# Communication_Main.net
KiCad netlist of a schematic drawn in Altium Designer
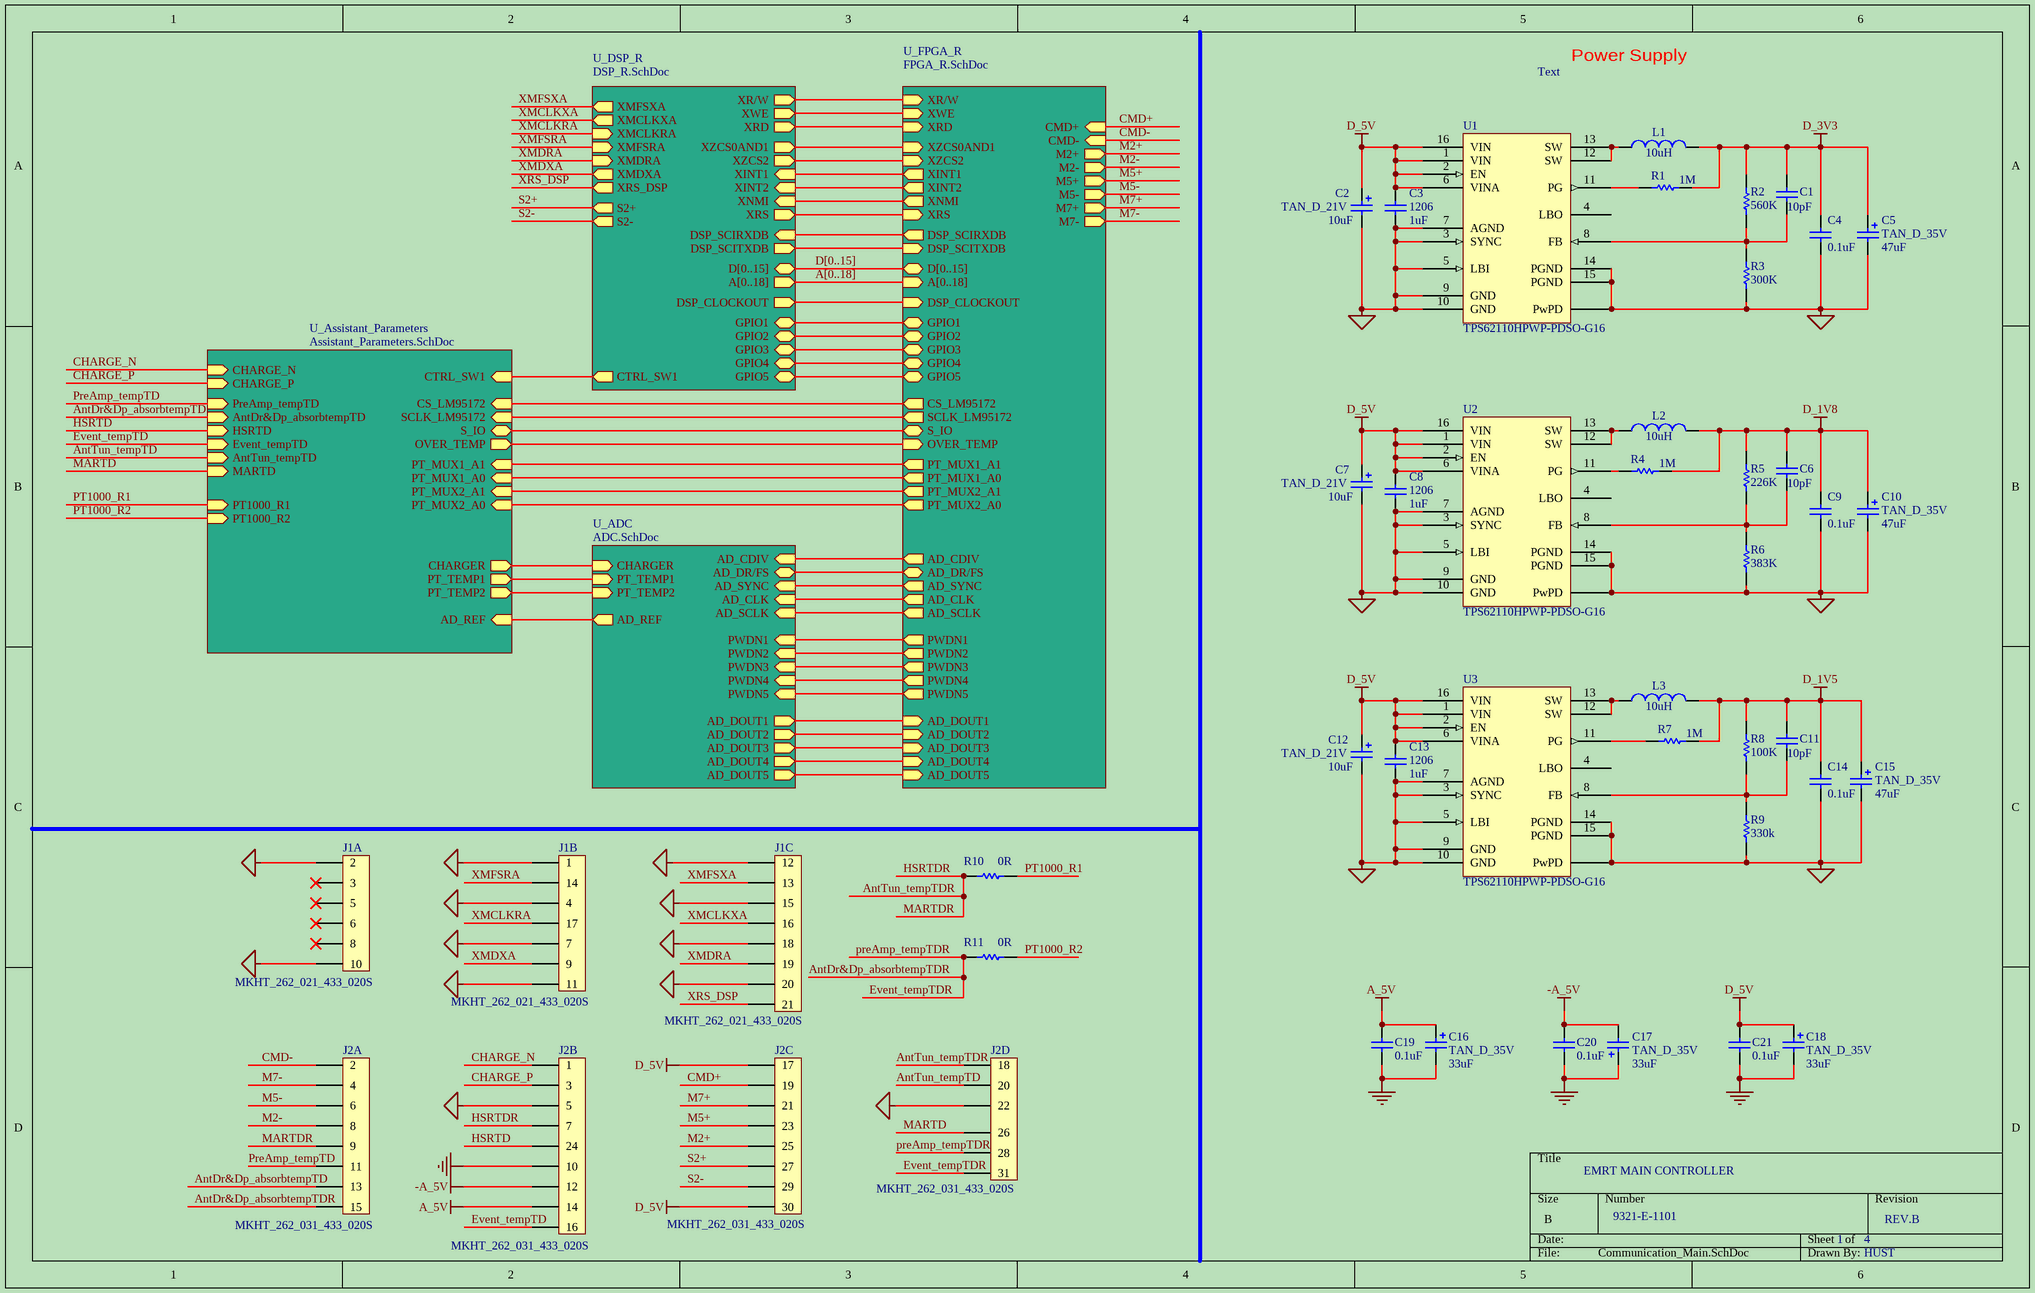
[diagram p0: Communication_Main.SchDoc]

(export (version "E")
  (design (tool "Eeschema 10.0.6"))
  (components
    (comp (ref "C1")
      (value "10pF")
      (footprint "CAPS0805_57")
      (description "Capacitor")
      (fields (field (name "PART NUMBER") "Y20025162") (field (name "Comment") "Cap"))
      (libsource (lib "Cap") (part "Cap"))
    )
    (comp (ref "C2")
      (value "TAN_D_21V")
      (footprint "EMRT MAIN CONTROLLER:CAPSP_2q2917")
      (description "Polarized Capacitor")
      (fields (field (name "ALTIUM_VALUE") "10uF") (field (name "PART NUMBER") "Y20024818"))
      (libsource (lib "电容") (part "Y20024818"))
    )
    (comp (ref "C3")
      (value "1206")
      (footprint "CAPS1206_43")
      (description "Capacitor")
      (fields (field (name "ALTIUM_VALUE") "1uF") (field (name "PART NUMBER") "Y20024113"))
      (libsource (lib "Cap") (part "Cap"))
    )
    (comp (ref "C4")
      (value "0.1uF")
      (footprint "CAPS0805_57")
      (description "Capacitor")
      (fields (field (name "PART NUMBER") "Y20025084") (field (name "Comment") "Cap"))
      (libsource (lib "Cap") (part "Cap"))
    )
    (comp (ref "C5")
      (value "TAN_D_35V")
      (footprint "CAPSP_2q2917")
      (description "Polarized Capacitor")
      (fields (field (name "ALTIUM_VALUE") "47uF") (field (name "PART NUMBER") "Y20024816"))
      (libsource (lib "Cap Pol") (part "Cap Pol"))
    )
    (comp (ref "C6")
      (value "10pF")
      (footprint "CAPS0805_57")
      (description "Capacitor")
      (fields (field (name "PART NUMBER") "Y20025162") (field (name "Comment") "Cap"))
      (libsource (lib "Cap") (part "Cap"))
    )
    (comp (ref "C7")
      (value "TAN_D_21V")
      (footprint "EMRT MAIN CONTROLLER:CAPSP_2q2917")
      (description "Polarized Capacitor")
      (fields (field (name "ALTIUM_VALUE") "10uF") (field (name "PART NUMBER") "Y20024818"))
      (libsource (lib "电容") (part "Y20024818"))
    )
    (comp (ref "C8")
      (value "1206")
      (footprint "CAPS1206_43")
      (description "Capacitor")
      (fields (field (name "ALTIUM_VALUE") "1uF") (field (name "PART NUMBER") "Y20024113"))
      (libsource (lib "Cap") (part "Cap"))
    )
    (comp (ref "C9")
      (value "0.1uF")
      (footprint "CAPS0805_57")
      (description "Capacitor")
      (fields (field (name "PART NUMBER") "Y20025084") (field (name "Comment") "Cap"))
      (libsource (lib "Cap") (part "Cap"))
    )
    (comp (ref "C10")
      (value "TAN_D_35V")
      (footprint "CAPSP_2q2917")
      (description "Polarized Capacitor")
      (fields (field (name "ALTIUM_VALUE") "47uF") (field (name "PART NUMBER") "Y20024816"))
      (libsource (lib "Cap Pol") (part "Cap Pol"))
    )
    (comp (ref "C11")
      (value "10pF")
      (footprint "CAPS0805_57")
      (description "Capacitor")
      (fields (field (name "PART NUMBER") "Y20025162") (field (name "Comment") "Cap"))
      (libsource (lib "Cap") (part "Cap"))
    )
    (comp (ref "C12")
      (value "TAN_D_21V")
      (footprint "EMRT MAIN CONTROLLER:CAPSP_2q2917")
      (description "Polarized Capacitor")
      (fields (field (name "ALTIUM_VALUE") "10uF") (field (name "PART NUMBER") "Y20024818"))
      (libsource (lib "电容") (part "Y20024818"))
    )
    (comp (ref "C13")
      (value "1206")
      (footprint "CAPS1206_43")
      (description "Capacitor")
      (fields (field (name "ALTIUM_VALUE") "1uF") (field (name "PART NUMBER") "Y20024113"))
      (libsource (lib "Cap") (part "Cap"))
    )
    (comp (ref "C14")
      (value "0.1uF")
      (footprint "CAPS0805_57")
      (description "Capacitor")
      (fields (field (name "PART NUMBER") "Y20025084") (field (name "Comment") "Cap"))
      (libsource (lib "Cap") (part "Cap"))
    )
    (comp (ref "C15")
      (value "TAN_D_35V")
      (footprint "CAPSP_2q2917")
      (description "Polarized Capacitor")
      (fields (field (name "ALTIUM_VALUE") "47uF") (field (name "PART NUMBER") "Y20024816"))
      (libsource (lib "Cap Pol") (part "Cap Pol"))
    )
    (comp (ref "C16")
      (value "TAN_D_35V")
      (footprint "CAPSP_2q2917")
      (description "Polarized Capacitor")
      (fields (field (name "ALTIUM_VALUE") "33uF") (field (name "PART NUMBER") "Y20024816"))
      (libsource (lib "Cap Pol") (part "Cap Pol"))
    )
    (comp (ref "C17")
      (value "TAN_D_35V")
      (footprint "CAPSP_2q2917")
      (description "Polarized Capacitor")
      (fields (field (name "ALTIUM_VALUE") "33uF") (field (name "PART NUMBER") "Y20024816"))
      (libsource (lib "Cap Pol") (part "Cap Pol"))
    )
    (comp (ref "C18")
      (value "TAN_D_35V")
      (footprint "CAPSP_2q2917")
      (description "Polarized Capacitor")
      (fields (field (name "ALTIUM_VALUE") "33uF") (field (name "PART NUMBER") "Y20024816"))
      (libsource (lib "Cap Pol") (part "Cap Pol"))
    )
    (comp (ref "C19")
      (value "0.1uF")
      (footprint "CAPS0805_57")
      (description "Capacitor")
      (fields (field (name "PART NUMBER") "Y20025084") (field (name "Comment") "Cap"))
      (libsource (lib "Cap") (part "Cap"))
    )
    (comp (ref "C20")
      (value "0.1uF")
      (footprint "CAPS0805_57")
      (description "Capacitor")
      (fields (field (name "PART NUMBER") "Y20025084") (field (name "Comment") "Cap"))
      (libsource (lib "Cap") (part "Cap"))
    )
    (comp (ref "C21")
      (value "0.1uF")
      (footprint "CAPS0805_57")
      (description "Capacitor")
      (fields (field (name "PART NUMBER") "Y20025084") (field (name "Comment") "Cap"))
      (libsource (lib "Cap") (part "Cap"))
    )
    (comp (ref "J1")
      (value "MKHT_262_021_433_020S")
      (footprint "MKHT_262_021_433_020S")
      (libsource (lib "srj") (part "MKHT_262_021_433_020S"))
    )
    (comp (ref "J2")
      (value "MKHT_262_031_433_020S")
      (footprint "MKHT_262_031_433_020S")
      (libsource (lib "srj") (part "MKHT_262_031_433_020S"))
    )
    (comp (ref "L1")
      (value "10uH")
      (footprint "Inductor_HT")
      (description "Inductor-1")
      (fields (field (name "PART NUMBER") "Y20028214") (field (name "Comment") "Inductor"))
      (libsource (lib "B82422H1103K000") (part "B82422H1103K000"))
    )
    (comp (ref "L2")
      (value "10uH")
      (footprint "Inductor_HT")
      (description "Inductor-1")
      (fields (field (name "PART NUMBER") "Y20028214") (field (name "Comment") "Inductor"))
      (libsource (lib "B82422H1103K000") (part "B82422H1103K000"))
    )
    (comp (ref "L3")
      (value "10uH")
      (footprint "Inductor_HT")
      (description "Inductor-1")
      (fields (field (name "PART NUMBER") "Y20028214") (field (name "Comment") "Inductor"))
      (libsource (lib "B82422H1103K000") (part "B82422H1103K000"))
    )
    (comp (ref "R1")
      (value "1M")
      (footprint "RESS0805")
      (description "Semiconductor Resistor")
      (fields
        (field (name "MANUFACTURER") "Generic Components")
        (field (name "Comment") "Res")
        (field (name "PUBLISHER") "Altium Hobart Technology Centre")
      )
      (libsource (lib "EMRT MAIN CONTROLLER") (part "Res"))
    )
    (comp (ref "R2")
      (value "560K")
      (footprint "RESS0805")
      (description "Semiconductor Resistor")
      (fields
        (field (name "MANUFACTURER") "Generic Components")
        (field (name "Comment") "Res")
        (field (name "PUBLISHER") "Altium Hobart Technology Centre")
      )
      (libsource (lib "EMRT MAIN CONTROLLER") (part "Res"))
    )
    (comp (ref "R3")
      (value "300K")
      (footprint "RESS0805")
      (description "Semiconductor Resistor")
      (fields
        (field (name "MANUFACTURER") "Generic Components")
        (field (name "Comment") "Res")
        (field (name "PUBLISHER") "Altium Hobart Technology Centre")
      )
      (libsource (lib "EMRT MAIN CONTROLLER") (part "Res"))
    )
    (comp (ref "R4")
      (value "1M")
      (footprint "RESS0805")
      (description "Semiconductor Resistor")
      (fields
        (field (name "MANUFACTURER") "Generic Components")
        (field (name "Comment") "Res")
        (field (name "PUBLISHER") "Altium Hobart Technology Centre")
      )
      (libsource (lib "EMRT MAIN CONTROLLER") (part "Res"))
    )
    (comp (ref "R5")
      (value "226K")
      (footprint "RESS0805")
      (description "Semiconductor Resistor")
      (fields
        (field (name "MANUFACTURER") "Generic Components")
        (field (name "Comment") "Res")
        (field (name "PUBLISHER") "Altium Hobart Technology Centre")
      )
      (libsource (lib "EMRT MAIN CONTROLLER") (part "Res"))
    )
    (comp (ref "R6")
      (value "383K")
      (footprint "RESS0805")
      (description "Semiconductor Resistor")
      (fields
        (field (name "MANUFACTURER") "Generic Components")
        (field (name "Comment") "Res")
        (field (name "PUBLISHER") "Altium Hobart Technology Centre")
      )
      (libsource (lib "EMRT MAIN CONTROLLER") (part "Res"))
    )
    (comp (ref "R7")
      (value "1M")
      (footprint "RESS0805")
      (description "Semiconductor Resistor")
      (fields
        (field (name "MANUFACTURER") "Generic Components")
        (field (name "Comment") "Res")
        (field (name "PUBLISHER") "Altium Hobart Technology Centre")
      )
      (libsource (lib "EMRT MAIN CONTROLLER") (part "Res"))
    )
    (comp (ref "R8")
      (value "100K")
      (footprint "RESS0805")
      (description "Semiconductor Resistor")
      (fields
        (field (name "MANUFACTURER") "Generic Components")
        (field (name "Comment") "Res")
        (field (name "PUBLISHER") "Altium Hobart Technology Centre")
      )
      (libsource (lib "EMRT MAIN CONTROLLER") (part "Res"))
    )
    (comp (ref "R9")
      (value "330k")
      (footprint "RESS0805")
      (description "Semiconductor Resistor")
      (fields
        (field (name "MANUFACTURER") "Generic Components")
        (field (name "Comment") "Res")
        (field (name "PUBLISHER") "Altium Hobart Technology Centre")
      )
      (libsource (lib "EMRT MAIN CONTROLLER") (part "Res"))
    )
    (comp (ref "R10")
      (value "0R")
      (footprint "RESS0805")
      (description "Semiconductor Resistor")
      (fields
        (field (name "MANUFACTURER") "Generic Components")
        (field (name "Comment") "Res")
        (field (name "PUBLISHER") "Altium Hobart Technology Centre")
      )
      (libsource (lib "EMRT MAIN CONTROLLER") (part "Res"))
    )
    (comp (ref "R11")
      (value "0R")
      (footprint "RESS0805")
      (description "Semiconductor Resistor")
      (fields
        (field (name "MANUFACTURER") "Generic Components")
        (field (name "Comment") "Res")
        (field (name "PUBLISHER") "Altium Hobart Technology Centre")
      )
      (libsource (lib "EMRT MAIN CONTROLLER") (part "Res"))
    )
    (comp (ref "U1")
      (value "TPS62110HPWP-PDSO-G16")
      (footprint "EMRT MAIN CONTROLLER:PWP16")
      (fields (field (name "PART NUMBER") "Y20033002"))
      (libsource (lib "TPS62110-HT") (part "TPS62110-HPWP"))
    )
    (comp (ref "U2")
      (value "TPS62110HPWP-PDSO-G16")
      (footprint "EMRT MAIN CONTROLLER:PWP16")
      (fields (field (name "PART NUMBER") "Y20033002"))
      (libsource (lib "TPS62110-HT") (part "TPS62110-HPWP"))
    )
    (comp (ref "U3")
      (value "TPS62110HPWP-PDSO-G16")
      (footprint "EMRT MAIN CONTROLLER:PWP16")
      (fields (field (name "PART NUMBER") "Y20033002"))
      (libsource (lib "TPS62110-HT") (part "TPS62110-HPWP"))
    )
  )
  (nets
    (net (code "36") (name "-A_5V") (class "Default")
      (node (ref "C17") (pin "2") (pinfunction "2_2") (pintype "passive"))
      (node (ref "C20") (pin "1") (pinfunction "1_1") (pintype "passive"))
      (node (ref "J2") (pin "12") (pinfunction "12_12") (pintype "passive"))
    )
    (net (code "49") (name "/AntDr&Dp_absorbtempTD") (class "Default")
      (node (ref "J2") (pin "13") (pinfunction "13_13") (pintype "passive"))
    )
    (net (code "50") (name "/AntDr&Dp_absorbtempTDR") (class "Default")
      (node (ref "J2") (pin "15") (pinfunction "15_15") (pintype "passive"))
      (node (ref "J2") (pin "28") (pinfunction "28_28") (pintype "passive"))
      (node (ref "J2") (pin "31") (pinfunction "31_31") (pintype "passive"))
      (node (ref "R11") (pin "2") (pinfunction "2_2") (pintype "passive"))
    )
    (net (code "51") (name "/AntTun_tempTD") (class "Default")
      (node (ref "J2") (pin "20") (pinfunction "20_20") (pintype "passive"))
    )
    (net (code "52") (name "/AntTun_tempTDR") (class "Default")
      (node (ref "J2") (pin "18") (pinfunction "18_18") (pintype "passive"))
      (node (ref "J2") (pin "7") (pinfunction "7_7") (pintype "passive"))
      (node (ref "J2") (pin "9") (pinfunction "9_9") (pintype "passive"))
      (node (ref "R10") (pin "2") (pinfunction "2_2") (pintype "passive"))
    )
    (net (code "54") (name "/CHARGE_N") (class "Default")
      (node (ref "J2") (pin "1") (pinfunction "1_1") (pintype "passive"))
    )
    (net (code "55") (name "/CHARGE_P") (class "Default")
      (node (ref "J2") (pin "3") (pinfunction "3_3") (pintype "passive"))
    )
    (net (code "56") (name "/CMD+") (class "Default")
      (node (ref "J2") (pin "19") (pinfunction "19_19") (pintype "passive"))
    )
    (net (code "57") (name "/CMD-") (class "Default")
      (node (ref "J2") (pin "2") (pinfunction "2_2") (pintype "passive"))
    )
    (net (code "64") (name "/Event_tempTD") (class "Default")
      (node (ref "J2") (pin "16") (pinfunction "16_16") (pintype "passive"))
    )
    (net (code "70") (name "/HSRTD") (class "Default")
      (node (ref "J2") (pin "24") (pinfunction "24_24") (pintype "passive"))
    )
    (net (code "71") (name "/M2+") (class "Default")
      (node (ref "J2") (pin "25") (pinfunction "25_25") (pintype "passive"))
    )
    (net (code "72") (name "/M2-") (class "Default")
      (node (ref "J2") (pin "8") (pinfunction "8_8") (pintype "passive"))
    )
    (net (code "73") (name "/M5+") (class "Default")
      (node (ref "J2") (pin "23") (pinfunction "23_23") (pintype "passive"))
    )
    (net (code "74") (name "/M5-") (class "Default")
      (node (ref "J2") (pin "6") (pinfunction "6_6") (pintype "passive"))
    )
    (net (code "75") (name "/M7+") (class "Default")
      (node (ref "J2") (pin "21") (pinfunction "21_21") (pintype "passive"))
    )
    (net (code "76") (name "/M7-") (class "Default")
      (node (ref "J2") (pin "4") (pinfunction "4_4") (pintype "passive"))
    )
    (net (code "77") (name "/MARTD") (class "Default")
      (node (ref "J2") (pin "26") (pinfunction "26_26") (pintype "passive"))
    )
    (net (code "79") (name "/PT1000_R1") (class "Default")
      (node (ref "R10") (pin "1") (pinfunction "1_1") (pintype "passive"))
    )
    (net (code "80") (name "/PT1000_R2") (class "Default")
      (node (ref "R11") (pin "1") (pinfunction "1_1") (pintype "passive"))
    )
    (net (code "92") (name "/PreAmp_tempTD") (class "Default")
      (node (ref "J2") (pin "11") (pinfunction "11_11") (pintype "passive"))
    )
    (net (code "93") (name "/S2+") (class "Default")
      (node (ref "J2") (pin "27") (pinfunction "27_27") (pintype "passive"))
    )
    (net (code "94") (name "/S2-") (class "Default")
      (node (ref "J2") (pin "29") (pinfunction "29_29") (pintype "passive"))
    )
    (net (code "99") (name "/XMCLKRA") (class "Default")
      (node (ref "J1") (pin "17") (pinfunction "17_17") (pintype "passive"))
    )
    (net (code "100") (name "/XMCLKXA") (class "Default")
      (node (ref "J1") (pin "16") (pinfunction "16_16") (pintype "passive"))
    )
    (net (code "101") (name "/XMDRA") (class "Default")
      (node (ref "J1") (pin "19") (pinfunction "19_19") (pintype "passive"))
    )
    (net (code "102") (name "/XMDXA") (class "Default")
      (node (ref "J1") (pin "9") (pinfunction "9_9") (pintype "passive"))
    )
    (net (code "103") (name "/XMFSRA") (class "Default")
      (node (ref "J1") (pin "14") (pinfunction "14_14") (pintype "passive"))
    )
    (net (code "104") (name "/XMFSXA") (class "Default")
      (node (ref "J1") (pin "13") (pinfunction "13_13") (pintype "passive"))
    )
    (net (code "108") (name "/XRS_DSP") (class "Default")
      (node (ref "J1") (pin "21") (pinfunction "21_21") (pintype "passive"))
    )
    (net (code "113") (name "A_5V") (class "Default")
      (node (ref "C16") (pin "1") (pinfunction "1_1") (pintype "passive"))
      (node (ref "C19") (pin "2") (pinfunction "2_2") (pintype "passive"))
      (node (ref "J2") (pin "14") (pinfunction "14_14") (pintype "passive"))
    )
    (net (code "114") (name "DGND") (class "Default")
      (node (ref "C10") (pin "2") (pinfunction "2_2") (pintype "passive"))
      (node (ref "C12") (pin "2") (pinfunction "2_2") (pintype "passive"))
      (node (ref "C13") (pin "1") (pinfunction "1_1") (pintype "passive"))
      (node (ref "C14") (pin "1") (pinfunction "1_1") (pintype "passive"))
      (node (ref "C15") (pin "2") (pinfunction "2_2") (pintype "passive"))
      (node (ref "C2") (pin "2") (pinfunction "2_2") (pintype "passive"))
      (node (ref "C3") (pin "1") (pinfunction "1_1") (pintype "passive"))
      (node (ref "C4") (pin "1") (pinfunction "1_1") (pintype "passive"))
      (node (ref "C5") (pin "2") (pinfunction "2_2") (pintype "passive"))
      (node (ref "C7") (pin "2") (pinfunction "2_2") (pintype "passive"))
      (node (ref "C8") (pin "1") (pinfunction "1_1") (pintype "passive"))
      (node (ref "C9") (pin "1") (pinfunction "1_1") (pintype "passive"))
      (node (ref "J1") (pin "1") (pinfunction "1_1") (pintype "passive"))
      (node (ref "J1") (pin "10") (pinfunction "10_10") (pintype "passive"))
      (node (ref "J1") (pin "11") (pinfunction "11_11") (pintype "passive"))
      (node (ref "J1") (pin "12") (pinfunction "12_12") (pintype "passive"))
      (node (ref "J1") (pin "15") (pinfunction "15_15") (pintype "passive"))
      (node (ref "J1") (pin "18") (pinfunction "18_18") (pintype "passive"))
      (node (ref "J1") (pin "2") (pinfunction "2_2") (pintype "passive"))
      (node (ref "J1") (pin "20") (pinfunction "20_20") (pintype "passive"))
      (node (ref "J1") (pin "4") (pinfunction "4_4") (pintype "passive"))
      (node (ref "J1") (pin "7") (pinfunction "7_7") (pintype "passive"))
      (node (ref "J2") (pin "22") (pinfunction "22_22") (pintype "passive"))
      (node (ref "J2") (pin "5") (pinfunction "5_5") (pintype "passive"))
      (node (ref "R3") (pin "1") (pinfunction "1_1") (pintype "passive"))
      (node (ref "R6") (pin "1") (pinfunction "1_1") (pintype "passive"))
      (node (ref "R9") (pin "1") (pinfunction "1_1") (pintype "passive"))
      (node (ref "U1") (pin "10") (pinfunction "GND_10") (pintype "passive"))
      (node (ref "U1") (pin "14") (pinfunction "PGND_14") (pintype "passive"))
      (node (ref "U1") (pin "15") (pinfunction "PGND_15") (pintype "passive"))
      (node (ref "U1") (pin "3") (pinfunction "SYNC_3") (pintype "input"))
      (node (ref "U1") (pin "5") (pinfunction "LBI_5") (pintype "input"))
      (node (ref "U1") (pin "7") (pinfunction "AGND_7") (pintype "power_in"))
      (node (ref "U1") (pin "9") (pinfunction "GND_9") (pintype "passive"))
      (node (ref "U1") (pin "PwPD") (pinfunction "PwPD_PwPD") (pintype "passive"))
      (node (ref "U2") (pin "10") (pinfunction "GND_10") (pintype "passive"))
      (node (ref "U2") (pin "14") (pinfunction "PGND_14") (pintype "passive"))
      (node (ref "U2") (pin "15") (pinfunction "PGND_15") (pintype "passive"))
      (node (ref "U2") (pin "3") (pinfunction "SYNC_3") (pintype "input"))
      (node (ref "U2") (pin "5") (pinfunction "LBI_5") (pintype "input"))
      (node (ref "U2") (pin "7") (pinfunction "AGND_7") (pintype "power_in"))
      (node (ref "U2") (pin "9") (pinfunction "GND_9") (pintype "passive"))
      (node (ref "U2") (pin "PwPD") (pinfunction "PwPD_PwPD") (pintype "passive"))
      (node (ref "U3") (pin "10") (pinfunction "GND_10") (pintype "passive"))
      (node (ref "U3") (pin "14") (pinfunction "PGND_14") (pintype "passive"))
      (node (ref "U3") (pin "15") (pinfunction "PGND_15") (pintype "passive"))
      (node (ref "U3") (pin "3") (pinfunction "SYNC_3") (pintype "input"))
      (node (ref "U3") (pin "5") (pinfunction "LBI_5") (pintype "input"))
      (node (ref "U3") (pin "7") (pinfunction "AGND_7") (pintype "power_in"))
      (node (ref "U3") (pin "9") (pinfunction "GND_9") (pintype "passive"))
      (node (ref "U3") (pin "PwPD") (pinfunction "PwPD_PwPD") (pintype "passive"))
    )
    (net (code "115") (name "D_1V5") (class "Default")
      (node (ref "C11") (pin "2") (pinfunction "2_2") (pintype "passive"))
      (node (ref "C14") (pin "2") (pinfunction "2_2") (pintype "passive"))
      (node (ref "C15") (pin "1") (pinfunction "1_1") (pintype "passive"))
      (node (ref "L3") (pin "2") (pinfunction "2_2") (pintype "passive"))
      (node (ref "R7") (pin "2") (pinfunction "2_2") (pintype "passive"))
      (node (ref "R8") (pin "2") (pinfunction "2_2") (pintype "passive"))
    )
    (net (code "116") (name "D_1V8") (class "Default")
      (node (ref "C10") (pin "1") (pinfunction "1_1") (pintype "passive"))
      (node (ref "C6") (pin "2") (pinfunction "2_2") (pintype "passive"))
      (node (ref "C9") (pin "2") (pinfunction "2_2") (pintype "passive"))
      (node (ref "L2") (pin "2") (pinfunction "2_2") (pintype "passive"))
      (node (ref "R4") (pin "2") (pinfunction "2_2") (pintype "passive"))
      (node (ref "R5") (pin "2") (pinfunction "2_2") (pintype "passive"))
    )
    (net (code "117") (name "D_3V3") (class "Default")
      (node (ref "C1") (pin "2") (pinfunction "2_2") (pintype "passive"))
      (node (ref "C4") (pin "2") (pinfunction "2_2") (pintype "passive"))
      (node (ref "C5") (pin "1") (pinfunction "1_1") (pintype "passive"))
      (node (ref "L1") (pin "2") (pinfunction "2_2") (pintype "passive"))
      (node (ref "R1") (pin "2") (pinfunction "2_2") (pintype "passive"))
      (node (ref "R2") (pin "2") (pinfunction "2_2") (pintype "passive"))
    )
    (net (code "118") (name "D_5V") (class "Default")
      (node (ref "C12") (pin "1") (pinfunction "1_1") (pintype "passive"))
      (node (ref "C13") (pin "2") (pinfunction "2_2") (pintype "passive"))
      (node (ref "C18") (pin "1") (pinfunction "1_1") (pintype "passive"))
      (node (ref "C2") (pin "1") (pinfunction "1_1") (pintype "passive"))
      (node (ref "C21") (pin "1") (pinfunction "1_1") (pintype "passive"))
      (node (ref "C3") (pin "2") (pinfunction "2_2") (pintype "passive"))
      (node (ref "C7") (pin "1") (pinfunction "1_1") (pintype "passive"))
      (node (ref "C8") (pin "2") (pinfunction "2_2") (pintype "passive"))
      (node (ref "J2") (pin "17") (pinfunction "17_17") (pintype "passive"))
      (node (ref "J2") (pin "30") (pinfunction "30_30") (pintype "passive"))
      (node (ref "U1") (pin "1") (pinfunction "VIN_1") (pintype "power_in"))
      (node (ref "U1") (pin "16") (pinfunction "VIN_16") (pintype "power_in"))
      (node (ref "U1") (pin "2") (pinfunction "EN_2") (pintype "input"))
      (node (ref "U1") (pin "6") (pinfunction "VINA_6") (pintype "power_in"))
      (node (ref "U2") (pin "1") (pinfunction "VIN_1") (pintype "power_in"))
      (node (ref "U2") (pin "16") (pinfunction "VIN_16") (pintype "power_in"))
      (node (ref "U2") (pin "2") (pinfunction "EN_2") (pintype "input"))
      (node (ref "U2") (pin "6") (pinfunction "VINA_6") (pintype "power_in"))
      (node (ref "U3") (pin "1") (pinfunction "VIN_1") (pintype "power_in"))
      (node (ref "U3") (pin "16") (pinfunction "VIN_16") (pintype "power_in"))
      (node (ref "U3") (pin "2") (pinfunction "EN_2") (pintype "input"))
      (node (ref "U3") (pin "6") (pinfunction "VINA_6") (pintype "power_in"))
    )
    (net (code "119") (name "GND") (class "Default")
      (node (ref "C16") (pin "2") (pinfunction "2_2") (pintype "passive"))
      (node (ref "C17") (pin "1") (pinfunction "1_1") (pintype "passive"))
      (node (ref "C18") (pin "2") (pinfunction "2_2") (pintype "passive"))
      (node (ref "C19") (pin "1") (pinfunction "1_1") (pintype "passive"))
      (node (ref "C20") (pin "2") (pinfunction "2_2") (pintype "passive"))
      (node (ref "C21") (pin "2") (pinfunction "2_2") (pintype "passive"))
      (node (ref "J2") (pin "10") (pinfunction "10_10") (pintype "passive"))
    )
    (net (code "120") (name "Net-(L1-Pad1)") (class "Default")
      (node (ref "L1") (pin "1") (pinfunction "1_1") (pintype "passive"))
      (node (ref "U1") (pin "12") (pinfunction "SW_12") (pintype "passive"))
      (node (ref "U1") (pin "13") (pinfunction "SW_13") (pintype "passive"))
    )
    (net (code "121") (name "Net-(L2-Pad1)") (class "Default")
      (node (ref "L2") (pin "1") (pinfunction "1_1") (pintype "passive"))
      (node (ref "U2") (pin "12") (pinfunction "SW_12") (pintype "passive"))
      (node (ref "U2") (pin "13") (pinfunction "SW_13") (pintype "passive"))
    )
    (net (code "122") (name "Net-(L3-Pad1)") (class "Default")
      (node (ref "L3") (pin "1") (pinfunction "1_1") (pintype "passive"))
      (node (ref "U3") (pin "12") (pinfunction "SW_12") (pintype "passive"))
      (node (ref "U3") (pin "13") (pinfunction "SW_13") (pintype "passive"))
    )
    (net (code "123") (name "Net-(U1-FB)") (class "Default")
      (node (ref "C1") (pin "1") (pinfunction "1_1") (pintype "passive"))
      (node (ref "R2") (pin "1") (pinfunction "1_1") (pintype "passive"))
      (node (ref "R3") (pin "2") (pinfunction "2_2") (pintype "passive"))
      (node (ref "U1") (pin "8") (pinfunction "FB_8") (pintype "input"))
    )
    (net (code "124") (name "Net-(U1-PG)") (class "Default")
      (node (ref "R1") (pin "1") (pinfunction "1_1") (pintype "passive"))
      (node (ref "U1") (pin "11") (pinfunction "PG_11") (pintype "output"))
    )
    (net (code "125") (name "Net-(U2-FB)") (class "Default")
      (node (ref "C6") (pin "1") (pinfunction "1_1") (pintype "passive"))
      (node (ref "R5") (pin "1") (pinfunction "1_1") (pintype "passive"))
      (node (ref "R6") (pin "2") (pinfunction "2_2") (pintype "passive"))
      (node (ref "U2") (pin "8") (pinfunction "FB_8") (pintype "input"))
    )
    (net (code "126") (name "Net-(U2-PG)") (class "Default")
      (node (ref "R4") (pin "1") (pinfunction "1_1") (pintype "passive"))
      (node (ref "U2") (pin "11") (pinfunction "PG_11") (pintype "output"))
    )
    (net (code "127") (name "Net-(U3-FB)") (class "Default")
      (node (ref "C11") (pin "1") (pinfunction "1_1") (pintype "passive"))
      (node (ref "R8") (pin "1") (pinfunction "1_1") (pintype "passive"))
      (node (ref "R9") (pin "2") (pinfunction "2_2") (pintype "passive"))
      (node (ref "U3") (pin "8") (pinfunction "FB_8") (pintype "input"))
    )
    (net (code "128") (name "Net-(U3-PG)") (class "Default")
      (node (ref "R7") (pin "1") (pinfunction "1_1") (pintype "passive"))
      (node (ref "U3") (pin "11") (pinfunction "PG_11") (pintype "output"))
    )
    (net (code "129") (name "unconnected-(J1-Pad3)") (class "Default")
      (node (ref "J1") (pin "3") (pinfunction "3_3") (pintype "passive+no_connect"))
    )
    (net (code "130") (name "unconnected-(J1-Pad5)") (class "Default")
      (node (ref "J1") (pin "5") (pinfunction "5_5") (pintype "passive+no_connect"))
    )
    (net (code "131") (name "unconnected-(J1-Pad6)") (class "Default")
      (node (ref "J1") (pin "6") (pinfunction "6_6") (pintype "passive+no_connect"))
    )
    (net (code "132") (name "unconnected-(J1-Pad8)") (class "Default")
      (node (ref "J1") (pin "8") (pinfunction "8_8") (pintype "passive+no_connect"))
    )
    (net (code "133") (name "unconnected-(U1-LBO-Pad4)") (class "Default")
      (node (ref "U1") (pin "4") (pinfunction "LBO_4") (pintype "passive"))
    )
    (net (code "134") (name "unconnected-(U2-LBO-Pad4)") (class "Default")
      (node (ref "U2") (pin "4") (pinfunction "LBO_4") (pintype "passive"))
    )
    (net (code "135") (name "unconnected-(U3-LBO-Pad4)") (class "Default")
      (node (ref "U3") (pin "4") (pinfunction "LBO_4") (pintype "passive"))
    )
  )
)
